# Fuel_Level_Monitoring_System.net
KiCad netlist of a schematic drawn in Altium Designer
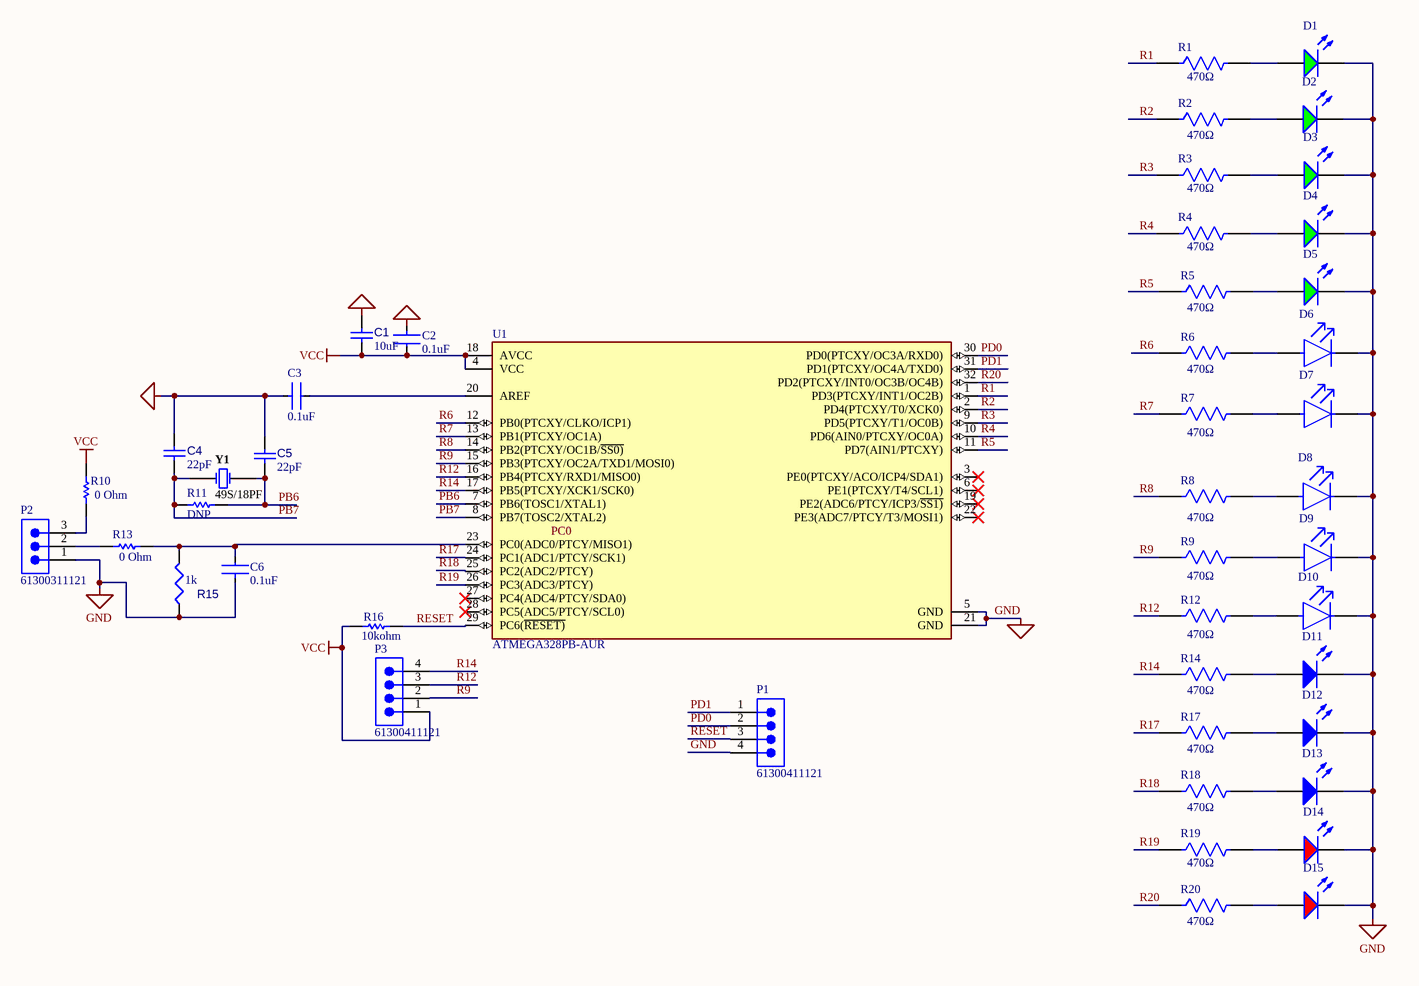
[diagram p0: Fuel Level Monitoring System.SchDoc]

(export (version "E")
  (design (tool "Eeschema 10.0.6"))
  (components
    (comp (ref "C1")
      (value "10uF")
      (footprint "CAPC0603(1608)100_L")
      (description "Chip Capacitor, 10µF +/-20%, 10V, 0603, Thickness 1 mm")
      (fields (field (name "TOLERANCE") "10%") (field (name "Comment") "Capacitor 10µF +/-20% 10V 0603"))
      (libsource (lib "Rajasekharmuthukuru") (part "CAP-NP-2"))
    )
    (comp (ref "C2")
      (value "0.1uF")
      (footprint "FP-CC0805-0_85-MFG")
      (description "CAP CER 0.1UF 50V X7R 0805")
      (fields (field (name "TOLERANCE") "0.1") (field (name "MANUFACTURER PART NUMBER") "CC0805KRX7R9BB104"))
      (libsource (lib "Altium Content Vault") (part "11868f565c42a9108669ba33697ecf6"))
    )
    (comp (ref "C3")
      (value "0.1uF")
      (footprint "FP-CC0805-0_85-MFG")
      (description "CAP CER 0.1UF 50V X7R 0805")
      (fields (field (name "TOLERANCE") "0.1") (field (name "MANUFACTURER PART NUMBER") "CC0805KRX7R9BB104"))
      (libsource (lib "Altium Content Vault") (part "11868f565c42a9108669ba33697ecf6"))
    )
    (comp (ref "C4")
      (value "22pF")
      (footprint "CAPC0402(1005)60_L")
      (description "Chip Capacitor, 22pF +/-10%, 50V, 0402, Thickness 0.6 mm")
      (fields (field (name "TOLERANCE") "10%") (field (name "Comment") "Capacitor 22pF +/-10% 50V 0402"))
      (libsource (lib "Rajasekharmuthukuru") (part "CAP-NP-2"))
    )
    (comp (ref "C5")
      (value "22pF")
      (footprint "CAPC0402(1005)60_L")
      (description "Chip Capacitor, 22pF +/-10%, 50V, 0402, Thickness 0.6 mm")
      (fields (field (name "TOLERANCE") "10%") (field (name "Comment") "Capacitor 22pF +/-10% 50V 0402"))
      (libsource (lib "Rajasekharmuthukuru") (part "CAP-NP-2"))
    )
    (comp (ref "C6")
      (value "0.1uF")
      (footprint "FP-CC0805-0_85-MFG")
      (description "CAP CER 0.1UF 50V X7R 0805")
      (fields (field (name "TOLERANCE") "0.1") (field (name "MANUFACTURER PART NUMBER") "CC0805KRX7R9BB104"))
      (libsource (lib "Altium Content Vault") (part "11868f565c42a9108669ba33697ecf6"))
    )
    (comp (ref "D1")
      (value "150120GS75000")
      (footprint "WL-SMCW_1206_150120xx75000")
      (description "WL-SMCW SMT Mono-Color Chip LED Waterclear")
      (libsource (lib "Altium Content Vault") (part "LED_Green_2A-1K"))
    )
    (comp (ref "D2")
      (value "150120GS75000")
      (footprint "WL-SMCW_1206_150120xx75000")
      (description "WL-SMCW SMT Mono-Color Chip LED Waterclear")
      (libsource (lib "Altium Content Vault") (part "LED_Green_2A-1K"))
    )
    (comp (ref "D3")
      (value "150120GS75000")
      (footprint "WL-SMCW_1206_150120xx75000")
      (description "WL-SMCW SMT Mono-Color Chip LED Waterclear")
      (libsource (lib "Altium Content Vault") (part "LED_Green_2A-1K"))
    )
    (comp (ref "D4")
      (value "150120GS75000")
      (footprint "WL-SMCW_1206_150120xx75000")
      (description "WL-SMCW SMT Mono-Color Chip LED Waterclear")
      (libsource (lib "Altium Content Vault") (part "LED_Green_2A-1K"))
    )
    (comp (ref "D5")
      (value "150120GS75000")
      (footprint "WL-SMCW_1206_150120xx75000")
      (description "WL-SMCW SMT Mono-Color Chip LED Waterclear")
      (libsource (lib "Altium Content Vault") (part "LED_Green_2A-1K"))
    )
    (comp (ref "D6")
      (value "LTST-C150KSKT")
      (footprint "FP-LTST-C150KSKT-MFG")
      (description "LED YELLOW CLEAR 1206 SMD")
      (libsource (lib "Altium Content Vault") (part "8706943c75ba83719d021d2fdc84c58"))
    )
    (comp (ref "D7")
      (value "LTST-C150KSKT")
      (footprint "FP-LTST-C150KSKT-MFG")
      (description "LED YELLOW CLEAR 1206 SMD")
      (libsource (lib "Altium Content Vault") (part "8706943c75ba83719d021d2fdc84c58"))
    )
    (comp (ref "D8")
      (value "LTST-C150KSKT")
      (footprint "FP-LTST-C150KSKT-MFG")
      (description "LED YELLOW CLEAR 1206 SMD")
      (libsource (lib "Altium Content Vault") (part "8706943c75ba83719d021d2fdc84c58"))
    )
    (comp (ref "D9")
      (value "LTST-C150KSKT")
      (footprint "FP-LTST-C150KSKT-MFG")
      (description "LED YELLOW CLEAR 1206 SMD")
      (libsource (lib "Altium Content Vault") (part "8706943c75ba83719d021d2fdc84c58"))
    )
    (comp (ref "D10")
      (value "LTST-C150KSKT")
      (footprint "FP-LTST-C150KSKT-MFG")
      (description "LED YELLOW CLEAR 1206 SMD")
      (libsource (lib "Altium Content Vault") (part "8706943c75ba83719d021d2fdc84c58"))
    )
    (comp (ref "D11")
      (value "150120BS75000")
      (footprint "WL-SMCW_1206_150120xx75000")
      (description "WL-SMCW SMT Mono-Color Chip LED Waterclear")
      (libsource (lib "Altium Content Vault") (part "LED_Blue_2A-1K"))
    )
    (comp (ref "D12")
      (value "150120BS75000")
      (footprint "WL-SMCW_1206_150120xx75000")
      (description "WL-SMCW SMT Mono-Color Chip LED Waterclear")
      (libsource (lib "Altium Content Vault") (part "LED_Blue_2A-1K"))
    )
    (comp (ref "D13")
      (value "150120BS75000")
      (footprint "WL-SMCW_1206_150120xx75000")
      (description "WL-SMCW SMT Mono-Color Chip LED Waterclear")
      (libsource (lib "Altium Content Vault") (part "LED_Blue_2A-1K"))
    )
    (comp (ref "D14")
      (value "150120RS75000")
      (footprint "WL-SMCW_1206_150120xx75000")
      (description "WL-SMCW SMT Mono-Color Chip LED Waterclear")
      (libsource (lib "Altium Content Vault") (part "LED_Red_2A-1K"))
    )
    (comp (ref "D15")
      (value "150120RS75000")
      (footprint "WL-SMCW_1206_150120xx75000")
      (description "WL-SMCW SMT Mono-Color Chip LED Waterclear")
      (libsource (lib "Altium Content Vault") (part "LED_Red_2A-1K"))
    )
    (comp (ref "P1")
      (value "61300411121")
      (footprint "61300411121")
      (libsource (lib "Altium Content Vault") (part "Header_Male_1R_04P"))
    )
    (comp (ref "P2")
      (value "61300311121")
      (footprint "61300311121")
      (libsource (lib "Altium Content Vault") (part "Header_Male_1R_03P"))
    )
    (comp (ref "P3")
      (value "61300411121")
      (footprint "61300411121")
      (libsource (lib "Altium Content Vault") (part "Header_Male_1R_04P"))
    )
    (comp (ref "R1")
      (value "470Ω")
      (footprint "FP-CRGCQ0805-IPC_C")
      (description "CRGCQ0805 470Ω 0.125W ±100ppm/°C 5% 150V")
      (fields (field (name "TOLERANCE") "0.05") (field (name "MANUFACTURER") "TE Connectivity"))
      (libsource (lib "Altium Content Vault") (part "1029c3af85768c4190bb7ad29bc67b5"))
    )
    (comp (ref "R2")
      (value "470Ω")
      (footprint "FP-CRGCQ0805-IPC_C")
      (description "CRGCQ0805 470Ω 0.125W ±100ppm/°C 5% 150V")
      (fields (field (name "TOLERANCE") "0.05") (field (name "MANUFACTURER") "TE Connectivity"))
      (libsource (lib "Altium Content Vault") (part "1029c3af85768c4190bb7ad29bc67b5"))
    )
    (comp (ref "R3")
      (value "470Ω")
      (footprint "FP-CRGCQ0805-IPC_C")
      (description "CRGCQ0805 470Ω 0.125W ±100ppm/°C 5% 150V")
      (fields (field (name "TOLERANCE") "0.05") (field (name "MANUFACTURER") "TE Connectivity"))
      (libsource (lib "Altium Content Vault") (part "1029c3af85768c4190bb7ad29bc67b5"))
    )
    (comp (ref "R4")
      (value "470Ω")
      (footprint "FP-CRGCQ0805-IPC_C")
      (description "CRGCQ0805 470Ω 0.125W ±100ppm/°C 5% 150V")
      (fields (field (name "TOLERANCE") "0.05") (field (name "MANUFACTURER") "TE Connectivity"))
      (libsource (lib "Altium Content Vault") (part "1029c3af85768c4190bb7ad29bc67b5"))
    )
    (comp (ref "R5")
      (value "CRGCQ0805J470R")
      (footprint "FP-CRGCQ0805-IPC_C")
      (description "CRGCQ0805 470Ω 0.125W ±100ppm/°C 5% 150V")
      (fields
        (field (name "TOLERANCE") "0.05")
        (field (name "RESISTANCE") "470Ω")
        (field (name "MANUFACTURER") "TE Connectivity")
      )
      (libsource (lib "Altium Content Vault") (part "1029c3af85768c4190bb7ad29bc67b5"))
    )
    (comp (ref "R6")
      (value "CRGCQ0805J470R")
      (footprint "FP-CRGCQ0805-IPC_C")
      (description "CRGCQ0805 470Ω 0.125W ±100ppm/°C 5% 150V")
      (fields
        (field (name "TOLERANCE") "0.05")
        (field (name "RESISTANCE") "470Ω")
        (field (name "MANUFACTURER") "TE Connectivity")
      )
      (libsource (lib "Altium Content Vault") (part "1029c3af85768c4190bb7ad29bc67b5"))
    )
    (comp (ref "R7")
      (value "CRGCQ0805J470R")
      (footprint "FP-CRGCQ0805-IPC_C")
      (description "CRGCQ0805 470Ω 0.125W ±100ppm/°C 5% 150V")
      (fields
        (field (name "TOLERANCE") "0.05")
        (field (name "RESISTANCE") "470Ω")
        (field (name "MANUFACTURER") "TE Connectivity")
      )
      (libsource (lib "Altium Content Vault") (part "1029c3af85768c4190bb7ad29bc67b5"))
    )
    (comp (ref "R8")
      (value "470Ω")
      (footprint "FP-CRGCQ0805-IPC_C")
      (description "CRGCQ0805 470Ω 0.125W ±100ppm/°C 5% 150V")
      (fields (field (name "TOLERANCE") "0.05") (field (name "MANUFACTURER") "TE Connectivity"))
      (libsource (lib "Altium Content Vault") (part "1029c3af85768c4190bb7ad29bc67b5"))
    )
    (comp (ref "R9")
      (value "CRGCQ0805J470R")
      (footprint "FP-CRGCQ0805-IPC_C")
      (description "CRGCQ0805 470Ω 0.125W ±100ppm/°C 5% 150V")
      (fields
        (field (name "TOLERANCE") "0.05")
        (field (name "RESISTANCE") "470Ω")
        (field (name "MANUFACTURER") "TE Connectivity")
      )
      (libsource (lib "Altium Content Vault") (part "1029c3af85768c4190bb7ad29bc67b5"))
    )
    (comp (ref "R10")
      (value "RC0805JR-070RL")
      (footprint "RESC2013X60X35ML10T20")
      (fields
        (field (name "RESISTANCE") "0 Ohm")
        (field (name "TOLERANCE") "5%")
        (field (name "MANUFACTURER") "Yageo")
      )
      (libsource (lib "Altium Content Vault") (part "RES-2"))
    )
    (comp (ref "R11")
      (value "RC0805JR-070RL")
      (footprint "RESC2013X60X35ML10T20")
      (fields
        (field (name "RESISTANCE") "DNP")
        (field (name "TOLERANCE") "5%")
        (field (name "MANUFACTURER") "Yageo")
      )
      (libsource (lib "Altium Content Vault") (part "RES-2"))
    )
    (comp (ref "R12")
      (value "470Ω")
      (footprint "FP-CRGCQ0805-IPC_C")
      (description "CRGCQ0805 470Ω 0.125W ±100ppm/°C 5% 150V")
      (fields (field (name "TOLERANCE") "0.05") (field (name "MANUFACTURER") "TE Connectivity"))
      (libsource (lib "Altium Content Vault") (part "1029c3af85768c4190bb7ad29bc67b5"))
    )
    (comp (ref "R13")
      (value "RC0805JR-070RL")
      (footprint "RESC2013X60X35ML10T20")
      (fields
        (field (name "RESISTANCE") "0 Ohm")
        (field (name "TOLERANCE") "5%")
        (field (name "MANUFACTURER") "Yageo")
      )
      (libsource (lib "Altium Content Vault") (part "RES-2"))
    )
    (comp (ref "R14")
      (value "CRGCQ0805J470R")
      (footprint "FP-CRGCQ0805-IPC_C")
      (description "CRGCQ0805 470Ω 0.125W ±100ppm/°C 5% 150V")
      (fields
        (field (name "TOLERANCE") "0.05")
        (field (name "RESISTANCE") "470Ω")
        (field (name "MANUFACTURER") "TE Connectivity")
      )
      (libsource (lib "Altium Content Vault") (part "1029c3af85768c4190bb7ad29bc67b5"))
    )
    (comp (ref "R15")
      (value "1k")
      (footprint "RESC0805(2012)_L")
      (description "Chip Resistor, 1 kOhms, +/-5%, 125 mW, -55 to 155 degC, 0805")
      (fields (field (name "TOLERANCE") "5%") (field (name "POWER") "125mW"))
      (libsource (lib "Rajasekharmuthukuru") (part "RES-2"))
    )
    (comp (ref "R16")
      (value "RC0805JR-0710KL")
      (footprint "RESC2013X60X35ML10T20")
      (description "Chip Resistor, 10 KOhm, +/- 5%, 0.125 W, -55 to 155 degC, 0805 (2012 Metric), RoHS, Tape and Reel")
      (fields (field (name "MANUFACTURER") "Yageo") (field (name "RESISTANCE") "10kohm"))
      (libsource (lib "Altium Content Vault") (part "RES-2"))
    )
    (comp (ref "R17")
      (value "CRGCQ0805J470R")
      (footprint "FP-CRGCQ0805-IPC_C")
      (description "CRGCQ0805 470Ω 0.125W ±100ppm/°C 5% 150V")
      (fields
        (field (name "TOLERANCE") "0.05")
        (field (name "RESISTANCE") "470Ω")
        (field (name "MANUFACTURER") "TE Connectivity")
      )
      (libsource (lib "Altium Content Vault") (part "1029c3af85768c4190bb7ad29bc67b5"))
    )
    (comp (ref "R18")
      (value "CRGCQ0805J470R")
      (footprint "FP-CRGCQ0805-IPC_C")
      (description "CRGCQ0805 470Ω 0.125W ±100ppm/°C 5% 150V")
      (fields
        (field (name "TOLERANCE") "0.05")
        (field (name "RESISTANCE") "470Ω")
        (field (name "MANUFACTURER") "TE Connectivity")
      )
      (libsource (lib "Altium Content Vault") (part "1029c3af85768c4190bb7ad29bc67b5"))
    )
    (comp (ref "R19")
      (value "CRGCQ0805J470R")
      (footprint "FP-CRGCQ0805-IPC_C")
      (description "CRGCQ0805 470Ω 0.125W ±100ppm/°C 5% 150V")
      (fields
        (field (name "TOLERANCE") "0.05")
        (field (name "RESISTANCE") "470Ω")
        (field (name "MANUFACTURER") "TE Connectivity")
      )
      (libsource (lib "Altium Content Vault") (part "1029c3af85768c4190bb7ad29bc67b5"))
    )
    (comp (ref "R20")
      (value "CRGCQ0805J470R")
      (footprint "FP-CRGCQ0805-IPC_C")
      (description "CRGCQ0805 470Ω 0.125W ±100ppm/°C 5% 150V")
      (fields
        (field (name "TOLERANCE") "0.05")
        (field (name "RESISTANCE") "470Ω")
        (field (name "MANUFACTURER") "TE Connectivity")
      )
      (libsource (lib "Altium Content Vault") (part "1029c3af85768c4190bb7ad29bc67b5"))
    )
    (comp (ref "U1")
      (value "ATMEGA328PB-AUR")
      (footprint "FP-C04-074-MFG")
      (description "IC MCU 8BIT 32KB FLASH 32TQFP")
      (fields
        (field (name "OCTOPART") "https://octopart.com/atmega328pb-aur-microchip-77760229")
        (field (name "MANUFACTURER") "Microchip")
      )
      (libsource (lib "Altium Content Vault") (part "d767239ca2d0de690368c988d022d7b"))
    )
    (comp (ref "Y1")
      (value "49S/18PF")
      (footprint "JPY-49S-18PF")
      (description "Crystal, 16 MHz, +/-20 ppm, 18 pF, -20 to 70 degC, 2-Pin THD, RoHS")
      (fields (field (name "MANUFACTURER") "Shenzhen Jingpengyuan"))
      (libsource (lib "Rajasekharmuthukuru") (part "XTAL-1-2-2"))
    )
  )
  (nets
    (net (code "1") (name "/PB6") (class "Default")
      (node (ref "C5") (pin "1") (pinfunction "1_1") (pintype "passive"))
      (node (ref "R11") (pin "1") (pinfunction "1_1") (pintype "passive"))
      (node (ref "U1") (pin "7") (pinfunction "PB6(TOSC1/XTAL1)_7") (pintype "bidirectional"))
      (node (ref "Y1") (pin "2") (pinfunction "2_2") (pintype "passive"))
    )
    (net (code "2") (name "/PB7") (class "Default")
      (node (ref "C4") (pin "1") (pinfunction "1_1") (pintype "passive"))
      (node (ref "R11") (pin "2") (pinfunction "2_2") (pintype "passive"))
      (node (ref "U1") (pin "8") (pinfunction "PB7(TOSC2/XTAL2)_8") (pintype "bidirectional"))
      (node (ref "Y1") (pin "1") (pinfunction "1_1") (pintype "passive"))
    )
    (net (code "4") (name "/PD0") (class "Default")
      (node (ref "P1") (pin "2") (pinfunction "2_2") (pintype "passive"))
      (node (ref "U1") (pin "30") (pinfunction "PD0(PTCXY/OC3A/RXD0)_30") (pintype "bidirectional"))
    )
    (net (code "5") (name "/PD1") (class "Default")
      (node (ref "P1") (pin "1") (pinfunction "1_1") (pintype "passive"))
      (node (ref "U1") (pin "31") (pinfunction "PD1(PTCXY/OC4A/TXD0)_31") (pintype "bidirectional"))
    )
    (net (code "6") (name "/R1") (class "Default")
      (node (ref "R1") (pin "1") (pinfunction "1_1") (pintype "passive"))
      (node (ref "U1") (pin "1") (pinfunction "PD3(PTCXY/INT1/OC2B)_1") (pintype "bidirectional"))
    )
    (net (code "7") (name "/R2") (class "Default")
      (node (ref "R2") (pin "1") (pinfunction "1_1") (pintype "passive"))
      (node (ref "U1") (pin "2") (pinfunction "PD4(PTCXY/T0/XCK0)_2") (pintype "bidirectional"))
    )
    (net (code "8") (name "/R3") (class "Default")
      (node (ref "R3") (pin "1") (pinfunction "1_1") (pintype "passive"))
      (node (ref "U1") (pin "9") (pinfunction "PD5(PTCXY/T1/OC0B)_9") (pintype "bidirectional"))
    )
    (net (code "9") (name "/R4") (class "Default")
      (node (ref "R4") (pin "1") (pinfunction "1_1") (pintype "passive"))
      (node (ref "U1") (pin "10") (pinfunction "PD6(AIN0/PTCXY/OC0A)_10") (pintype "bidirectional"))
    )
    (net (code "10") (name "/R5") (class "Default")
      (node (ref "R5") (pin "1") (pinfunction "1_1") (pintype "passive"))
      (node (ref "U1") (pin "11") (pinfunction "PD7(AIN1/PTCXY)_11") (pintype "bidirectional"))
    )
    (net (code "11") (name "/R6") (class "Default")
      (node (ref "R6") (pin "1") (pinfunction "1_1") (pintype "passive"))
      (node (ref "U1") (pin "12") (pinfunction "PB0(PTCXY/CLKO/ICP1)_12") (pintype "bidirectional"))
    )
    (net (code "12") (name "/R7") (class "Default")
      (node (ref "R7") (pin "1") (pinfunction "1_1") (pintype "passive"))
      (node (ref "U1") (pin "13") (pinfunction "PB1(PTCXY/OC1A)_13") (pintype "bidirectional"))
    )
    (net (code "13") (name "/R8") (class "Default")
      (node (ref "R8") (pin "1") (pinfunction "1_1") (pintype "passive"))
      (node (ref "U1") (pin "14") (pinfunction "PB2(PTCXY/OC1B/~{SS0)}_14") (pintype "bidirectional"))
    )
    (net (code "14") (name "/R9") (class "Default")
      (node (ref "P3") (pin "2") (pinfunction "2_2") (pintype "passive"))
      (node (ref "R9") (pin "1") (pinfunction "1_1") (pintype "passive"))
      (node (ref "U1") (pin "15") (pinfunction "PB3(PTCXY/OC2A/TXD1/MOSI0)_15") (pintype "bidirectional"))
    )
    (net (code "15") (name "/R12") (class "Default")
      (node (ref "P3") (pin "3") (pinfunction "3_3") (pintype "passive"))
      (node (ref "R12") (pin "1") (pinfunction "1_1") (pintype "passive"))
      (node (ref "U1") (pin "16") (pinfunction "PB4(PTCXY/RXD1/MISO0)_16") (pintype "bidirectional"))
    )
    (net (code "16") (name "/R14") (class "Default")
      (node (ref "P3") (pin "4") (pinfunction "4_4") (pintype "passive"))
      (node (ref "R14") (pin "1") (pinfunction "1_1") (pintype "passive"))
      (node (ref "U1") (pin "17") (pinfunction "PB5(PTCXY/XCK1/SCK0)_17") (pintype "bidirectional"))
    )
    (net (code "17") (name "/R17") (class "Default")
      (node (ref "R17") (pin "1") (pinfunction "1_1") (pintype "passive"))
      (node (ref "U1") (pin "24") (pinfunction "PC1(ADC1/PTCY/SCK1)_24") (pintype "bidirectional"))
    )
    (net (code "18") (name "/R18") (class "Default")
      (node (ref "R18") (pin "1") (pinfunction "1_1") (pintype "passive"))
      (node (ref "U1") (pin "25") (pinfunction "PC2(ADC2/PTCY)_25") (pintype "bidirectional"))
    )
    (net (code "19") (name "/R19") (class "Default")
      (node (ref "R19") (pin "1") (pinfunction "1_1") (pintype "passive"))
      (node (ref "U1") (pin "26") (pinfunction "PC3(ADC3/PTCY)_26") (pintype "bidirectional"))
    )
    (net (code "20") (name "/R20") (class "Default")
      (node (ref "R20") (pin "1") (pinfunction "1_1") (pintype "passive"))
      (node (ref "U1") (pin "32") (pinfunction "PD2(PTCXY/INT0/OC3B/OC4B)_32") (pintype "bidirectional"))
    )
    (net (code "21") (name "/RESET") (class "Default")
      (node (ref "P1") (pin "3") (pinfunction "3_3") (pintype "passive"))
      (node (ref "R16") (pin "1") (pinfunction "1_1") (pintype "passive"))
      (node (ref "U1") (pin "29") (pinfunction "PC6(~{RESET)}_29") (pintype "bidirectional"))
    )
    (net (code "22") (name "GND") (class "Default")
      (node (ref "C1") (pin "2") (pinfunction "2_2") (pintype "passive"))
      (node (ref "C2") (pin "1") (pinfunction "1_1") (pintype "passive"))
      (node (ref "C3") (pin "1") (pinfunction "1_1") (pintype "passive"))
      (node (ref "C4") (pin "2") (pinfunction "2_2") (pintype "passive"))
      (node (ref "C5") (pin "2") (pinfunction "2_2") (pintype "passive"))
      (node (ref "C6") (pin "1") (pinfunction "1_1") (pintype "passive"))
      (node (ref "D1") (pin "1") (pinfunction "K_1") (pintype "passive"))
      (node (ref "D10") (pin "1") (pinfunction "C_1") (pintype "passive"))
      (node (ref "D11") (pin "1") (pinfunction "K_1") (pintype "passive"))
      (node (ref "D12") (pin "1") (pinfunction "K_1") (pintype "passive"))
      (node (ref "D13") (pin "1") (pinfunction "K_1") (pintype "passive"))
      (node (ref "D14") (pin "1") (pinfunction "K_1") (pintype "passive"))
      (node (ref "D15") (pin "1") (pinfunction "K_1") (pintype "passive"))
      (node (ref "D2") (pin "1") (pinfunction "K_1") (pintype "passive"))
      (node (ref "D3") (pin "1") (pinfunction "K_1") (pintype "passive"))
      (node (ref "D4") (pin "1") (pinfunction "K_1") (pintype "passive"))
      (node (ref "D5") (pin "1") (pinfunction "K_1") (pintype "passive"))
      (node (ref "D6") (pin "1") (pinfunction "C_1") (pintype "passive"))
      (node (ref "D7") (pin "1") (pinfunction "C_1") (pintype "passive"))
      (node (ref "D8") (pin "1") (pinfunction "C_1") (pintype "passive"))
      (node (ref "D9") (pin "1") (pinfunction "C_1") (pintype "passive"))
      (node (ref "P1") (pin "4") (pinfunction "4_4") (pintype "passive"))
      (node (ref "P2") (pin "1") (pinfunction "1_1") (pintype "passive"))
      (node (ref "R15") (pin "1") (pinfunction "1_1") (pintype "passive"))
      (node (ref "U1") (pin "21") (pinfunction "GND_21") (pintype "power_in"))
      (node (ref "U1") (pin "5") (pinfunction "GND_5") (pintype "power_in"))
    )
    (net (code "23") (name "Net-(D1-A)") (class "Default")
      (node (ref "D1") (pin "2") (pinfunction "A_2") (pintype "passive"))
      (node (ref "R1") (pin "2") (pinfunction "2_2") (pintype "passive"))
    )
    (net (code "24") (name "Net-(D2-A)") (class "Default")
      (node (ref "D2") (pin "2") (pinfunction "A_2") (pintype "passive"))
      (node (ref "R2") (pin "2") (pinfunction "2_2") (pintype "passive"))
    )
    (net (code "25") (name "Net-(D3-A)") (class "Default")
      (node (ref "D3") (pin "2") (pinfunction "A_2") (pintype "passive"))
      (node (ref "R3") (pin "2") (pinfunction "2_2") (pintype "passive"))
    )
    (net (code "26") (name "Net-(D4-A)") (class "Default")
      (node (ref "D4") (pin "2") (pinfunction "A_2") (pintype "passive"))
      (node (ref "R4") (pin "2") (pinfunction "2_2") (pintype "passive"))
    )
    (net (code "27") (name "Net-(D5-A)") (class "Default")
      (node (ref "D5") (pin "2") (pinfunction "A_2") (pintype "passive"))
      (node (ref "R5") (pin "2") (pinfunction "2_2") (pintype "passive"))
    )
    (net (code "28") (name "Net-(D6-A)") (class "Default")
      (node (ref "D6") (pin "2") (pinfunction "A_2") (pintype "passive"))
      (node (ref "R6") (pin "2") (pinfunction "2_2") (pintype "passive"))
    )
    (net (code "29") (name "Net-(D7-A)") (class "Default")
      (node (ref "D7") (pin "2") (pinfunction "A_2") (pintype "passive"))
      (node (ref "R7") (pin "2") (pinfunction "2_2") (pintype "passive"))
    )
    (net (code "30") (name "Net-(D8-A)") (class "Default")
      (node (ref "D8") (pin "2") (pinfunction "A_2") (pintype "passive"))
      (node (ref "R8") (pin "2") (pinfunction "2_2") (pintype "passive"))
    )
    (net (code "31") (name "Net-(D9-A)") (class "Default")
      (node (ref "D9") (pin "2") (pinfunction "A_2") (pintype "passive"))
      (node (ref "R9") (pin "2") (pinfunction "2_2") (pintype "passive"))
    )
    (net (code "32") (name "Net-(D10-A)") (class "Default")
      (node (ref "D10") (pin "2") (pinfunction "A_2") (pintype "passive"))
      (node (ref "R12") (pin "2") (pinfunction "2_2") (pintype "passive"))
    )
    (net (code "33") (name "Net-(D11-A)") (class "Default")
      (node (ref "D11") (pin "2") (pinfunction "A_2") (pintype "passive"))
      (node (ref "R14") (pin "2") (pinfunction "2_2") (pintype "passive"))
    )
    (net (code "34") (name "Net-(D12-A)") (class "Default")
      (node (ref "D12") (pin "2") (pinfunction "A_2") (pintype "passive"))
      (node (ref "R17") (pin "2") (pinfunction "2_2") (pintype "passive"))
    )
    (net (code "35") (name "Net-(D13-A)") (class "Default")
      (node (ref "D13") (pin "2") (pinfunction "A_2") (pintype "passive"))
      (node (ref "R18") (pin "2") (pinfunction "2_2") (pintype "passive"))
    )
    (net (code "36") (name "Net-(D14-A)") (class "Default")
      (node (ref "D14") (pin "2") (pinfunction "A_2") (pintype "passive"))
      (node (ref "R19") (pin "2") (pinfunction "2_2") (pintype "passive"))
    )
    (net (code "37") (name "Net-(D15-A)") (class "Default")
      (node (ref "D15") (pin "2") (pinfunction "A_2") (pintype "passive"))
      (node (ref "R20") (pin "2") (pinfunction "2_2") (pintype "passive"))
    )
    (net (code "38") (name "Net-(P2-Pad2)") (class "Default")
      (node (ref "P2") (pin "2") (pinfunction "2_2") (pintype "passive"))
      (node (ref "R13") (pin "1") (pinfunction "1_1") (pintype "passive"))
    )
    (net (code "39") (name "Net-(P2-Pad3)") (class "Default")
      (node (ref "P2") (pin "3") (pinfunction "3_3") (pintype "passive"))
      (node (ref "R10") (pin "1") (pinfunction "1_1") (pintype "passive"))
    )
    (net (code "40") (name "Net-(U1-AREF)") (class "Default")
      (node (ref "C3") (pin "2") (pinfunction "2_2") (pintype "passive"))
      (node (ref "U1") (pin "20") (pinfunction "AREF_20") (pintype "power_in"))
    )
    (net (code "41") (name "Net-(U1-PC0(ADC0{slash}PTCY{slash}MISO1))") (class "Default")
      (node (ref "C6") (pin "2") (pinfunction "2_2") (pintype "passive"))
      (node (ref "R13") (pin "2") (pinfunction "2_2") (pintype "passive"))
      (node (ref "R15") (pin "2") (pinfunction "2_2") (pintype "passive"))
      (node (ref "U1") (pin "23") (pinfunction "PC0(ADC0/PTCY/MISO1)_23") (pintype "bidirectional"))
    )
    (net (code "42") (name "VCC") (class "Default")
      (node (ref "C1") (pin "1") (pinfunction "1_1") (pintype "passive"))
      (node (ref "C2") (pin "2") (pinfunction "2_2") (pintype "passive"))
      (node (ref "P3") (pin "1") (pinfunction "1_1") (pintype "passive"))
      (node (ref "R10") (pin "2") (pinfunction "2_2") (pintype "passive"))
      (node (ref "R16") (pin "2") (pinfunction "2_2") (pintype "passive"))
      (node (ref "U1") (pin "18") (pinfunction "AVCC_18") (pintype "power_in"))
      (node (ref "U1") (pin "4") (pinfunction "VCC_4") (pintype "power_in"))
    )
    (net (code "43") (name "unconnected-(U1-PC4(ADC4{slash}PTCY{slash}SDA0)-Pad27)") (class "Default")
      (node (ref "U1") (pin "27") (pinfunction "PC4(ADC4/PTCY/SDA0)_27") (pintype "bidirectional+no_connect"))
    )
    (net (code "44") (name "unconnected-(U1-PC5(ADC5{slash}PTCY{slash}SCL0)-Pad28)") (class "Default")
      (node (ref "U1") (pin "28") (pinfunction "PC5(ADC5/PTCY/SCL0)_28") (pintype "bidirectional+no_connect"))
    )
    (net (code "45") (name "unconnected-(U1-PE0(PTCXY{slash}ACO{slash}ICP4{slash}SDA1)-Pad3)") (class "Default")
      (node (ref "U1") (pin "3") (pinfunction "PE0(PTCXY/ACO/ICP4/SDA1)_3") (pintype "bidirectional+no_connect"))
    )
    (net (code "46") (name "unconnected-(U1-PE1(PTCXY{slash}T4{slash}SCL1)-Pad6)") (class "Default")
      (node (ref "U1") (pin "6") (pinfunction "PE1(PTCXY/T4/SCL1)_6") (pintype "bidirectional+no_connect"))
    )
    (net (code "47") (name "unconnected-(U1-PE2(ADC6{slash}PTCY{slash}ICP3{slash}~{SS1)}-Pad19)") (class "Default")
      (node (ref "U1") (pin "19") (pinfunction "PE2(ADC6/PTCY/ICP3/~{SS1)}_19") (pintype "bidirectional+no_connect"))
    )
    (net (code "48") (name "unconnected-(U1-PE3(ADC7{slash}PTCY{slash}T3{slash}MOSI1)-Pad22)") (class "Default")
      (node (ref "U1") (pin "22") (pinfunction "PE3(ADC7/PTCY/T3/MOSI1)_22") (pintype "bidirectional+no_connect"))
    )
  )
)
